# 17-FPGA-02b.net
KiCad netlist of a schematic drawn in Altium Designer
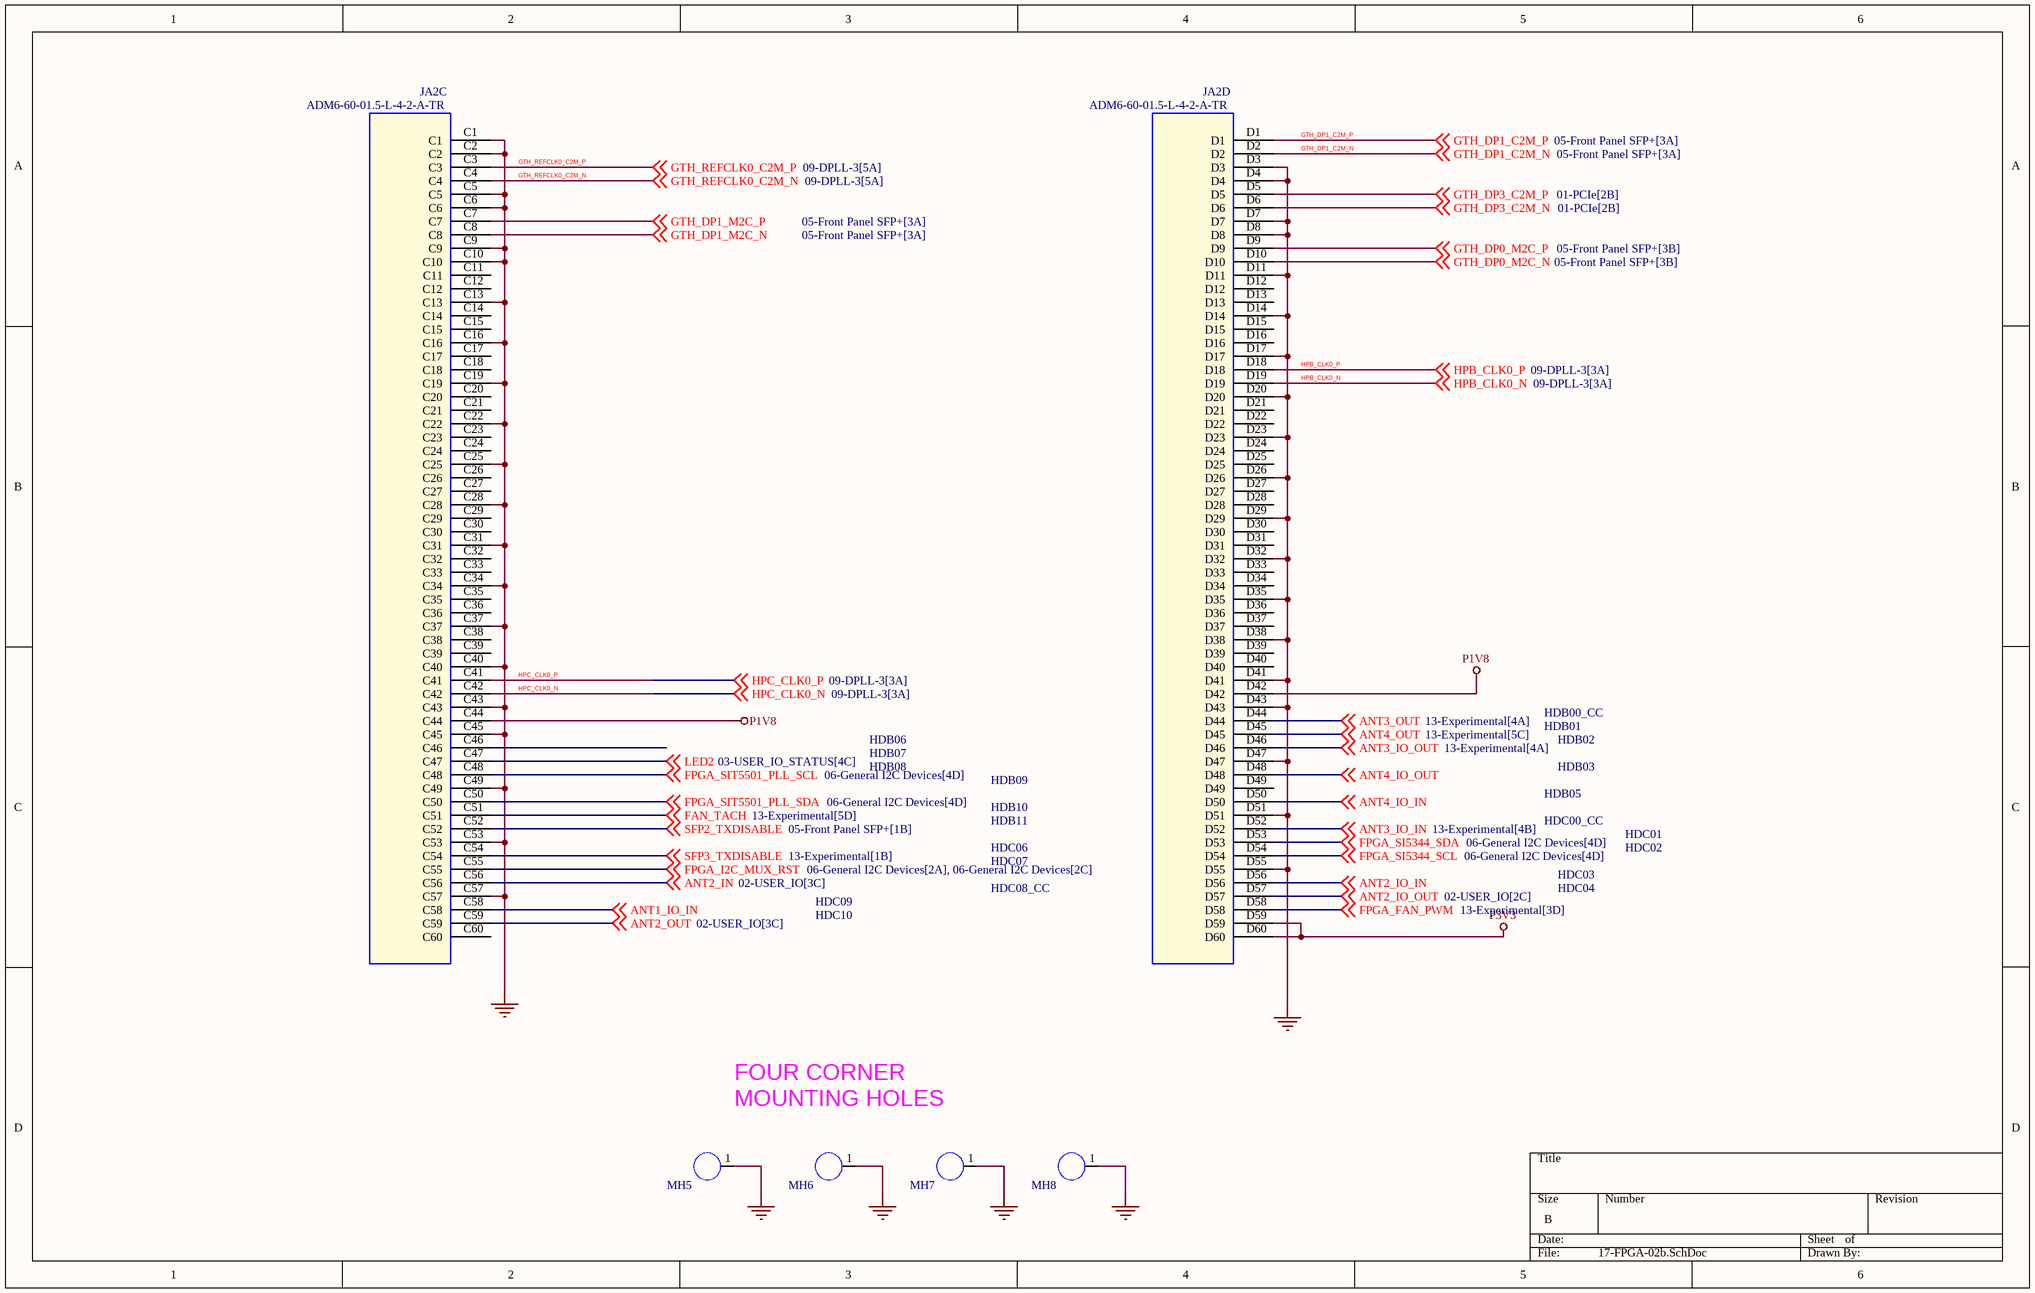
[diagram p0: 17-FPGA-02b.SchDoc]

(export (version "E")
  (design (tool "Eeschema 10.0.6"))
  (components
    (comp (ref "JA2")
      (value "ADM6-60-01.5-L-4-2-A-TR")
      (footprint "CON_SAMTEC_ADM6_60_4")
      (description "Conn Rcpt Male Vert 240 Pos 4x60 0.635mm P Black SMT")
      (fields (field (name "MANUFACTURER") "Samtec Inc.") (field (name "AGILE PART NUMBER") "CON-00383-01"))
      (libsource (lib "*") (part "SAMTEC-ADx6-60X4"))
    )
    (comp (ref "MH5")
      (value "MH_NP_M3_SO_600")
      (footprint "MH_NP_M3_SO_600")
      (description "MOUNTING HOLE, NON-PLATED 3.4MM HOLE")
      (libsource (lib "*") (part "HOLE"))
    )
    (comp (ref "MH6")
      (value "MH_NP_M3_SO_600")
      (footprint "MH_NP_M3_SO_600")
      (description "MOUNTING HOLE, NON-PLATED 3.4MM HOLE")
      (libsource (lib "*") (part "HOLE"))
    )
    (comp (ref "MH7")
      (value "MH_NP_M3_SO_600")
      (footprint "MH_NP_M3_SO_600")
      (description "MOUNTING HOLE, NON-PLATED 3.4MM HOLE")
      (libsource (lib "*") (part "HOLE"))
    )
    (comp (ref "MH8")
      (value "MH_NP_M3_SO_600")
      (footprint "MH_NP_M3_SO_600")
      (description "MOUNTING HOLE, NON-PLATED 3.4MM HOLE")
      (libsource (lib "*") (part "HOLE"))
    )
  )
  (nets
    (net (code "1") (name "ANT1_IO_IN") (class "Default")
      (node (ref "JA2") (pin "C58") (pinfunction "C58_C58") (pintype "passive"))
    )
    (net (code "2") (name "ANT2_IN") (class "Default")
      (node (ref "JA2") (pin "C56") (pinfunction "C56_C56") (pintype "passive"))
    )
    (net (code "3") (name "ANT2_IO_IN") (class "Default")
      (node (ref "JA2") (pin "D56") (pinfunction "D56_D56") (pintype "passive"))
    )
    (net (code "4") (name "ANT2_IO_OUT") (class "Default")
      (node (ref "JA2") (pin "D57") (pinfunction "D57_D57") (pintype "passive"))
    )
    (net (code "5") (name "ANT2_OUT") (class "Default")
      (node (ref "JA2") (pin "C59") (pinfunction "C59_C59") (pintype "passive"))
    )
    (net (code "6") (name "ANT3_IO_IN") (class "Default")
      (node (ref "JA2") (pin "D52") (pinfunction "D52_D52") (pintype "passive"))
    )
    (net (code "7") (name "ANT3_IO_OUT") (class "Default")
      (node (ref "JA2") (pin "D46") (pinfunction "D46_D46") (pintype "passive"))
    )
    (net (code "8") (name "ANT3_OUT") (class "Default")
      (node (ref "JA2") (pin "D44") (pinfunction "D44_D44") (pintype "passive"))
    )
    (net (code "9") (name "ANT4_IO_IN") (class "Default")
      (node (ref "JA2") (pin "D50") (pinfunction "D50_D50") (pintype "passive"))
    )
    (net (code "10") (name "ANT4_IO_OUT") (class "Default")
      (node (ref "JA2") (pin "D48") (pinfunction "D48_D48") (pintype "passive"))
    )
    (net (code "11") (name "ANT4_OUT") (class "Default")
      (node (ref "JA2") (pin "D45") (pinfunction "D45_D45") (pintype "passive"))
    )
    (net (code "12") (name "FAN_TACH") (class "Default")
      (node (ref "JA2") (pin "C51") (pinfunction "C51_C51") (pintype "passive"))
    )
    (net (code "13") (name "FPGA_FAN_PWM") (class "Default")
      (node (ref "JA2") (pin "D58") (pinfunction "D58_D58") (pintype "passive"))
    )
    (net (code "14") (name "FPGA_I2C_MUX_RST") (class "Default")
      (node (ref "JA2") (pin "C55") (pinfunction "C55_C55") (pintype "passive"))
    )
    (net (code "15") (name "FPGA_SI5344_SCL") (class "Default")
      (node (ref "JA2") (pin "D54") (pinfunction "D54_D54") (pintype "passive"))
    )
    (net (code "16") (name "FPGA_SI5344_SDA") (class "Default")
      (node (ref "JA2") (pin "D53") (pinfunction "D53_D53") (pintype "passive"))
    )
    (net (code "17") (name "FPGA_SIT5501_PLL_SCL") (class "Default")
      (node (ref "JA2") (pin "C48") (pinfunction "C48_C48") (pintype "passive"))
    )
    (net (code "18") (name "FPGA_SIT5501_PLL_SDA") (class "Default")
      (node (ref "JA2") (pin "C50") (pinfunction "C50_C50") (pintype "passive"))
    )
    (net (code "19") (name "GND") (class "Default")
      (node (ref "JA2") (pin "C1") (pinfunction "C1_C1") (pintype "passive"))
      (node (ref "JA2") (pin "C10") (pinfunction "C10_C10") (pintype "passive"))
      (node (ref "JA2") (pin "C13") (pinfunction "C13_C13") (pintype "passive"))
      (node (ref "JA2") (pin "C16") (pinfunction "C16_C16") (pintype "passive"))
      (node (ref "JA2") (pin "C19") (pinfunction "C19_C19") (pintype "passive"))
      (node (ref "JA2") (pin "C2") (pinfunction "C2_C2") (pintype "passive"))
      (node (ref "JA2") (pin "C22") (pinfunction "C22_C22") (pintype "passive"))
      (node (ref "JA2") (pin "C25") (pinfunction "C25_C25") (pintype "passive"))
      (node (ref "JA2") (pin "C28") (pinfunction "C28_C28") (pintype "passive"))
      (node (ref "JA2") (pin "C31") (pinfunction "C31_C31") (pintype "passive"))
      (node (ref "JA2") (pin "C34") (pinfunction "C34_C34") (pintype "passive"))
      (node (ref "JA2") (pin "C37") (pinfunction "C37_C37") (pintype "passive"))
      (node (ref "JA2") (pin "C40") (pinfunction "C40_C40") (pintype "passive"))
      (node (ref "JA2") (pin "C43") (pinfunction "C43_C43") (pintype "passive"))
      (node (ref "JA2") (pin "C45") (pinfunction "C45_C45") (pintype "passive"))
      (node (ref "JA2") (pin "C49") (pinfunction "C49_C49") (pintype "passive"))
      (node (ref "JA2") (pin "C5") (pinfunction "C5_C5") (pintype "passive"))
      (node (ref "JA2") (pin "C53") (pinfunction "C53_C53") (pintype "passive"))
      (node (ref "JA2") (pin "C57") (pinfunction "C57_C57") (pintype "passive"))
      (node (ref "JA2") (pin "C6") (pinfunction "C6_C6") (pintype "passive"))
      (node (ref "JA2") (pin "C9") (pinfunction "C9_C9") (pintype "passive"))
      (node (ref "JA2") (pin "D11") (pinfunction "D11_D11") (pintype "passive"))
      (node (ref "JA2") (pin "D14") (pinfunction "D14_D14") (pintype "passive"))
      (node (ref "JA2") (pin "D17") (pinfunction "D17_D17") (pintype "passive"))
      (node (ref "JA2") (pin "D20") (pinfunction "D20_D20") (pintype "passive"))
      (node (ref "JA2") (pin "D23") (pinfunction "D23_D23") (pintype "passive"))
      (node (ref "JA2") (pin "D26") (pinfunction "D26_D26") (pintype "passive"))
      (node (ref "JA2") (pin "D29") (pinfunction "D29_D29") (pintype "passive"))
      (node (ref "JA2") (pin "D3") (pinfunction "D3_D3") (pintype "passive"))
      (node (ref "JA2") (pin "D32") (pinfunction "D32_D32") (pintype "passive"))
      (node (ref "JA2") (pin "D35") (pinfunction "D35_D35") (pintype "passive"))
      (node (ref "JA2") (pin "D38") (pinfunction "D38_D38") (pintype "passive"))
      (node (ref "JA2") (pin "D4") (pinfunction "D4_D4") (pintype "passive"))
      (node (ref "JA2") (pin "D41") (pinfunction "D41_D41") (pintype "passive"))
      (node (ref "JA2") (pin "D43") (pinfunction "D43_D43") (pintype "passive"))
      (node (ref "JA2") (pin "D47") (pinfunction "D47_D47") (pintype "passive"))
      (node (ref "JA2") (pin "D51") (pinfunction "D51_D51") (pintype "passive"))
      (node (ref "JA2") (pin "D55") (pinfunction "D55_D55") (pintype "passive"))
      (node (ref "JA2") (pin "D7") (pinfunction "D7_D7") (pintype "passive"))
      (node (ref "JA2") (pin "D8") (pinfunction "D8_D8") (pintype "passive"))
      (node (ref "MH5") (pin "1") (pinfunction "1_1") (pintype "passive"))
      (node (ref "MH6") (pin "1") (pinfunction "1_1") (pintype "passive"))
      (node (ref "MH7") (pin "1") (pinfunction "1_1") (pintype "passive"))
      (node (ref "MH8") (pin "1") (pinfunction "1_1") (pintype "passive"))
    )
    (net (code "20") (name "GTH_DP0_M2C_N") (class "Default")
      (node (ref "JA2") (pin "D10") (pinfunction "D10_D10") (pintype "passive"))
    )
    (net (code "21") (name "GTH_DP0_M2C_P") (class "Default")
      (node (ref "JA2") (pin "D9") (pinfunction "D9_D9") (pintype "passive"))
    )
    (net (code "22") (name "GTH_DP1_C2M_N") (class "Default")
      (node (ref "JA2") (pin "D2") (pinfunction "D2_D2") (pintype "passive"))
    )
    (net (code "23") (name "GTH_DP1_C2M_P") (class "Default")
      (node (ref "JA2") (pin "D1") (pinfunction "D1_D1") (pintype "passive"))
    )
    (net (code "24") (name "GTH_DP1_M2C_N") (class "Default")
      (node (ref "JA2") (pin "C8") (pinfunction "C8_C8") (pintype "passive"))
    )
    (net (code "25") (name "GTH_DP1_M2C_P") (class "Default")
      (node (ref "JA2") (pin "C7") (pinfunction "C7_C7") (pintype "passive"))
    )
    (net (code "26") (name "GTH_DP3_C2M_N") (class "Default")
      (node (ref "JA2") (pin "D6") (pinfunction "D6_D6") (pintype "passive"))
    )
    (net (code "27") (name "GTH_DP3_C2M_P") (class "Default")
      (node (ref "JA2") (pin "D5") (pinfunction "D5_D5") (pintype "passive"))
    )
    (net (code "28") (name "GTH_REFCLK0_C2M_N") (class "Default")
      (node (ref "JA2") (pin "C4") (pinfunction "C4_C4") (pintype "passive"))
    )
    (net (code "29") (name "GTH_REFCLK0_C2M_P") (class "Default")
      (node (ref "JA2") (pin "C3") (pinfunction "C3_C3") (pintype "passive"))
    )
    (net (code "30") (name "HPB_CLK0_N") (class "Default")
      (node (ref "JA2") (pin "D19") (pinfunction "D19_D19") (pintype "passive"))
    )
    (net (code "31") (name "HPB_CLK0_P") (class "Default")
      (node (ref "JA2") (pin "D18") (pinfunction "D18_D18") (pintype "passive"))
    )
    (net (code "32") (name "HPC_CLK0_N") (class "Default")
      (node (ref "JA2") (pin "C42") (pinfunction "C42_C42") (pintype "passive"))
    )
    (net (code "33") (name "HPC_CLK0_P") (class "Default")
      (node (ref "JA2") (pin "C41") (pinfunction "C41_C41") (pintype "passive"))
    )
    (net (code "34") (name "LED2") (class "Default")
      (node (ref "JA2") (pin "C47") (pinfunction "C47_C47") (pintype "passive"))
    )
    (net (code "35") (name "P1V8") (class "Default")
      (node (ref "JA2") (pin "C44") (pinfunction "C44_C44") (pintype "passive"))
      (node (ref "JA2") (pin "D42") (pinfunction "D42_D42") (pintype "passive"))
    )
    (net (code "36") (name "P3V3") (class "Default")
      (node (ref "JA2") (pin "D59") (pinfunction "D59_D59") (pintype "passive"))
      (node (ref "JA2") (pin "D60") (pinfunction "D60_D60") (pintype "passive"))
    )
    (net (code "37") (name "SFP2_TXDISABLE") (class "Default")
      (node (ref "JA2") (pin "C52") (pinfunction "C52_C52") (pintype "passive"))
    )
    (net (code "38") (name "SFP3_TXDISABLE") (class "Default")
      (node (ref "JA2") (pin "C54") (pinfunction "C54_C54") (pintype "passive"))
    )
    (net (code "39") (name "unconnected-(JA2-PadC11)") (class "Default")
      (node (ref "JA2") (pin "C11") (pinfunction "C11_C11") (pintype "passive"))
    )
    (net (code "40") (name "unconnected-(JA2-PadC12)") (class "Default")
      (node (ref "JA2") (pin "C12") (pinfunction "C12_C12") (pintype "passive"))
    )
    (net (code "41") (name "unconnected-(JA2-PadC14)") (class "Default")
      (node (ref "JA2") (pin "C14") (pinfunction "C14_C14") (pintype "passive"))
    )
    (net (code "42") (name "unconnected-(JA2-PadC15)") (class "Default")
      (node (ref "JA2") (pin "C15") (pinfunction "C15_C15") (pintype "passive"))
    )
    (net (code "43") (name "unconnected-(JA2-PadC17)") (class "Default")
      (node (ref "JA2") (pin "C17") (pinfunction "C17_C17") (pintype "passive"))
    )
    (net (code "44") (name "unconnected-(JA2-PadC18)") (class "Default")
      (node (ref "JA2") (pin "C18") (pinfunction "C18_C18") (pintype "passive"))
    )
    (net (code "45") (name "unconnected-(JA2-PadC20)") (class "Default")
      (node (ref "JA2") (pin "C20") (pinfunction "C20_C20") (pintype "passive"))
    )
    (net (code "46") (name "unconnected-(JA2-PadC21)") (class "Default")
      (node (ref "JA2") (pin "C21") (pinfunction "C21_C21") (pintype "passive"))
    )
    (net (code "47") (name "unconnected-(JA2-PadC23)") (class "Default")
      (node (ref "JA2") (pin "C23") (pinfunction "C23_C23") (pintype "passive"))
    )
    (net (code "48") (name "unconnected-(JA2-PadC24)") (class "Default")
      (node (ref "JA2") (pin "C24") (pinfunction "C24_C24") (pintype "passive"))
    )
    (net (code "49") (name "unconnected-(JA2-PadC26)") (class "Default")
      (node (ref "JA2") (pin "C26") (pinfunction "C26_C26") (pintype "passive"))
    )
    (net (code "50") (name "unconnected-(JA2-PadC27)") (class "Default")
      (node (ref "JA2") (pin "C27") (pinfunction "C27_C27") (pintype "passive"))
    )
    (net (code "51") (name "unconnected-(JA2-PadC29)") (class "Default")
      (node (ref "JA2") (pin "C29") (pinfunction "C29_C29") (pintype "passive"))
    )
    (net (code "52") (name "unconnected-(JA2-PadC30)") (class "Default")
      (node (ref "JA2") (pin "C30") (pinfunction "C30_C30") (pintype "passive"))
    )
    (net (code "53") (name "unconnected-(JA2-PadC32)") (class "Default")
      (node (ref "JA2") (pin "C32") (pinfunction "C32_C32") (pintype "passive"))
    )
    (net (code "54") (name "unconnected-(JA2-PadC33)") (class "Default")
      (node (ref "JA2") (pin "C33") (pinfunction "C33_C33") (pintype "passive"))
    )
    (net (code "55") (name "unconnected-(JA2-PadC35)") (class "Default")
      (node (ref "JA2") (pin "C35") (pinfunction "C35_C35") (pintype "passive"))
    )
    (net (code "56") (name "unconnected-(JA2-PadC36)") (class "Default")
      (node (ref "JA2") (pin "C36") (pinfunction "C36_C36") (pintype "passive"))
    )
    (net (code "57") (name "unconnected-(JA2-PadC38)") (class "Default")
      (node (ref "JA2") (pin "C38") (pinfunction "C38_C38") (pintype "passive"))
    )
    (net (code "58") (name "unconnected-(JA2-PadC39)") (class "Default")
      (node (ref "JA2") (pin "C39") (pinfunction "C39_C39") (pintype "passive"))
    )
    (net (code "59") (name "unconnected-(JA2-PadC46)") (class "Default")
      (node (ref "JA2") (pin "C46") (pinfunction "C46_C46") (pintype "passive"))
    )
    (net (code "60") (name "unconnected-(JA2-PadC60)") (class "Default")
      (node (ref "JA2") (pin "C60") (pinfunction "C60_C60") (pintype "passive"))
    )
    (net (code "61") (name "unconnected-(JA2-PadD12)") (class "Default")
      (node (ref "JA2") (pin "D12") (pinfunction "D12_D12") (pintype "passive"))
    )
    (net (code "62") (name "unconnected-(JA2-PadD13)") (class "Default")
      (node (ref "JA2") (pin "D13") (pinfunction "D13_D13") (pintype "passive"))
    )
    (net (code "63") (name "unconnected-(JA2-PadD15)") (class "Default")
      (node (ref "JA2") (pin "D15") (pinfunction "D15_D15") (pintype "passive"))
    )
    (net (code "64") (name "unconnected-(JA2-PadD16)") (class "Default")
      (node (ref "JA2") (pin "D16") (pinfunction "D16_D16") (pintype "passive"))
    )
    (net (code "65") (name "unconnected-(JA2-PadD21)") (class "Default")
      (node (ref "JA2") (pin "D21") (pinfunction "D21_D21") (pintype "passive"))
    )
    (net (code "66") (name "unconnected-(JA2-PadD22)") (class "Default")
      (node (ref "JA2") (pin "D22") (pinfunction "D22_D22") (pintype "passive"))
    )
    (net (code "67") (name "unconnected-(JA2-PadD24)") (class "Default")
      (node (ref "JA2") (pin "D24") (pinfunction "D24_D24") (pintype "passive"))
    )
    (net (code "68") (name "unconnected-(JA2-PadD25)") (class "Default")
      (node (ref "JA2") (pin "D25") (pinfunction "D25_D25") (pintype "passive"))
    )
    (net (code "69") (name "unconnected-(JA2-PadD27)") (class "Default")
      (node (ref "JA2") (pin "D27") (pinfunction "D27_D27") (pintype "passive"))
    )
    (net (code "70") (name "unconnected-(JA2-PadD28)") (class "Default")
      (node (ref "JA2") (pin "D28") (pinfunction "D28_D28") (pintype "passive"))
    )
    (net (code "71") (name "unconnected-(JA2-PadD30)") (class "Default")
      (node (ref "JA2") (pin "D30") (pinfunction "D30_D30") (pintype "passive"))
    )
    (net (code "72") (name "unconnected-(JA2-PadD31)") (class "Default")
      (node (ref "JA2") (pin "D31") (pinfunction "D31_D31") (pintype "passive"))
    )
    (net (code "73") (name "unconnected-(JA2-PadD33)") (class "Default")
      (node (ref "JA2") (pin "D33") (pinfunction "D33_D33") (pintype "passive"))
    )
    (net (code "74") (name "unconnected-(JA2-PadD34)") (class "Default")
      (node (ref "JA2") (pin "D34") (pinfunction "D34_D34") (pintype "passive"))
    )
    (net (code "75") (name "unconnected-(JA2-PadD36)") (class "Default")
      (node (ref "JA2") (pin "D36") (pinfunction "D36_D36") (pintype "passive"))
    )
    (net (code "76") (name "unconnected-(JA2-PadD37)") (class "Default")
      (node (ref "JA2") (pin "D37") (pinfunction "D37_D37") (pintype "passive"))
    )
    (net (code "77") (name "unconnected-(JA2-PadD39)") (class "Default")
      (node (ref "JA2") (pin "D39") (pinfunction "D39_D39") (pintype "passive"))
    )
    (net (code "78") (name "unconnected-(JA2-PadD40)") (class "Default")
      (node (ref "JA2") (pin "D40") (pinfunction "D40_D40") (pintype "passive"))
    )
    (net (code "79") (name "unconnected-(JA2-PadD49)") (class "Default")
      (node (ref "JA2") (pin "D49") (pinfunction "D49_D49") (pintype "passive"))
    )
  )
)
